# IMU.net
KiCad netlist of a schematic drawn in Altium Designer
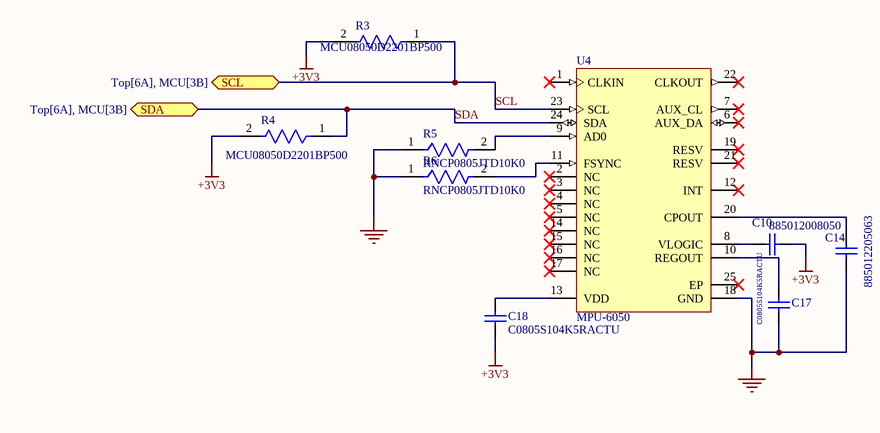
[diagram p0: IMU.SchDoc]

(export (version "E")
  (design (tool "Eeschema 10.0.6"))
  (components
    (comp (ref "C10")
      (value "885012008050")
      (footprint "WCAP-CSGP_1206_L3.2W1.6H0.8")
      (description "WCAP-CSGP 1206 (3216Metric) Ceramic Capacitor 0.126Lx0.063W 3.20mmx1.60mm C0G NP0 ±5% 1500pF")
      (fields (field (name "TOLERANCE") "5%"))
      (libsource (lib "Altium Content Vault") (part "Capacitor_Non-Polarized"))
    )
    (comp (ref "C14")
      (value "885012205063")
      (footprint "WCAP-CSGP_0402_L1W0.5H0.5")
      (description "Cap Ceramic 0.0022uF 50V X7R 10% Pad SMD 0402 125C T/R")
      (fields (field (name "TOLERANCE") "10%"))
      (libsource (lib "Altium Content Vault") (part "Capacitor_Non-Polarized"))
    )
    (comp (ref "C17")
      (value "C0805S104K5RACTU")
      (footprint "CAPC2013X145X50NL20T25")
      (fields (field (name "MANUFACTURER") "Kemet"))
      (libsource (lib "Altium Content Vault") (part "CAP"))
    )
    (comp (ref "C18")
      (value "C0805S104K5RACTU")
      (footprint "CAPC2013X145X50NL20T25")
      (fields (field (name "MANUFACTURER") "Kemet"))
      (libsource (lib "Altium Content Vault") (part "CAP"))
    )
    (comp (ref "R3")
      (value "MCU08050D2201BP500")
      (footprint "FP-MCU0805-MFG")
      (description "RES 1.05K OHM 0.5% 1/5W 0805")
      (fields (field (name "TOLERANCE") "0.1%"))
      (libsource (lib "Altium Content Vault") (part "1029c3af85768c4190bb7ad29bc67b5"))
    )
    (comp (ref "R4")
      (value "MCU08050D2201BP500")
      (footprint "FP-MCU0805-MFG")
      (description "RES 1.05K OHM 0.5% 1/5W 0805")
      (fields (field (name "TOLERANCE") "0.1%"))
      (libsource (lib "Altium Content Vault") (part "1029c3af85768c4190bb7ad29bc67b5"))
    )
    (comp (ref "R5")
      (value "RNCP0805JTD10K0")
      (footprint "FP-RNCP0805-IPC_B")
      (description "10kΩ ±5% 0.25W 0805 High Power Anti-Sulfur Thin Film Chip Resistor")
      (fields (field (name "TOLERANCE") "5%"))
      (libsource (lib "Altium Content Vault") (part "1029c3af85768c4190bb7ad29bc67b5"))
    )
    (comp (ref "R6")
      (value "RNCP0805JTD10K0")
      (footprint "FP-RNCP0805-IPC_B")
      (description "10kΩ ±5% 0.25W 0805 High Power Anti-Sulfur Thin Film Chip Resistor")
      (fields (field (name "TOLERANCE") "5%"))
      (libsource (lib "Altium Content Vault") (part "1029c3af85768c4190bb7ad29bc67b5"))
    )
    (comp (ref "U4")
      (value "MPU-6050")
      (footprint "IS-QFN-24_V")
      (fields (field (name "MANUFACTURER") "InvenSense"))
      (libsource (lib "Altium Content Vault") (part "IS-MPU-6050-QFN-24"))
    )
  )
  (nets
    (net (code "1") (name "+3V3") (class "Default")
      (node (ref "C10") (pin "2") (pinfunction "2_2") (pintype "passive"))
      (node (ref "C18") (pin "1") (pinfunction "1_1") (pintype "passive"))
      (node (ref "R3") (pin "2") (pinfunction "2_2") (pintype "passive"))
      (node (ref "R4") (pin "2") (pinfunction "2_2") (pintype "passive"))
    )
    (net (code "2") (name "/SCL") (class "Default")
      (node (ref "R3") (pin "1") (pinfunction "1_1") (pintype "passive"))
      (node (ref "U4") (pin "23") (pinfunction "SCL_23") (pintype "input"))
    )
    (net (code "3") (name "/SDA") (class "Default")
      (node (ref "R4") (pin "1") (pinfunction "1_1") (pintype "passive"))
      (node (ref "U4") (pin "24") (pinfunction "SDA_24") (pintype "bidirectional"))
    )
    (net (code "4") (name "<NO NET>") (class "Default")
      (node (ref "C14") (pin "1") (pinfunction "1_1") (pintype "passive"))
      (node (ref "C17") (pin "1") (pinfunction "1_1") (pintype "passive"))
      (node (ref "R5") (pin "1") (pinfunction "1_1") (pintype "passive"))
      (node (ref "R6") (pin "1") (pinfunction "1_1") (pintype "passive"))
      (node (ref "U4") (pin "18") (pinfunction "GND_18") (pintype "power_in"))
    )
    (net (code "5") (name "Net-(U4-AD0)") (class "Default")
      (node (ref "R5") (pin "2") (pinfunction "2_2") (pintype "passive"))
      (node (ref "U4") (pin "9") (pinfunction "AD0_9") (pintype "input"))
    )
    (net (code "6") (name "Net-(U4-CPOUT)") (class "Default")
      (node (ref "C14") (pin "2") (pinfunction "2_2") (pintype "passive"))
      (node (ref "U4") (pin "20") (pinfunction "CPOUT_20") (pintype "passive"))
    )
    (net (code "7") (name "Net-(U4-FSYNC)") (class "Default")
      (node (ref "R6") (pin "2") (pinfunction "2_2") (pintype "passive"))
      (node (ref "U4") (pin "11") (pinfunction "FSYNC_11") (pintype "input"))
    )
    (net (code "8") (name "Net-(U4-REGOUT)") (class "Default")
      (node (ref "C17") (pin "2") (pinfunction "2_2") (pintype "passive"))
      (node (ref "U4") (pin "10") (pinfunction "REGOUT_10") (pintype "passive"))
    )
    (net (code "9") (name "Net-(U4-VDD)") (class "Default")
      (node (ref "C18") (pin "2") (pinfunction "2_2") (pintype "passive"))
      (node (ref "U4") (pin "13") (pinfunction "VDD_13") (pintype "power_in"))
    )
    (net (code "10") (name "Net-(U4-VLOGIC)") (class "Default")
      (node (ref "C10") (pin "1") (pinfunction "1_1") (pintype "passive"))
      (node (ref "U4") (pin "8") (pinfunction "VLOGIC_8") (pintype "power_in"))
    )
    (net (code "11") (name "unconnected-(U4-AUX_CL-Pad7)") (class "Default")
      (node (ref "U4") (pin "7") (pinfunction "AUX_CL_7") (pintype "output+no_connect"))
    )
    (net (code "12") (name "unconnected-(U4-AUX_DA-Pad6)") (class "Default")
      (node (ref "U4") (pin "6") (pinfunction "AUX_DA_6") (pintype "bidirectional+no_connect"))
    )
    (net (code "13") (name "unconnected-(U4-CLKIN-Pad1)") (class "Default")
      (node (ref "U4") (pin "1") (pinfunction "CLKIN_1") (pintype "input+no_connect"))
    )
    (net (code "14") (name "unconnected-(U4-CLKOUT-Pad22)") (class "Default")
      (node (ref "U4") (pin "22") (pinfunction "CLKOUT_22") (pintype "output+no_connect"))
    )
    (net (code "15") (name "unconnected-(U4-EP-Pad25)") (class "Default")
      (node (ref "U4") (pin "25") (pinfunction "EP_25") (pintype "power_in+no_connect"))
    )
    (net (code "16") (name "unconnected-(U4-INT-Pad12)") (class "Default")
      (node (ref "U4") (pin "12") (pinfunction "INT_12") (pintype "open_collector+no_connect"))
    )
    (net (code "17") (name "unconnected-(U4-NC-Pad2)") (class "Default")
      (node (ref "U4") (pin "2") (pinfunction "NC_2") (pintype "passive+no_connect"))
    )
    (net (code "18") (name "unconnected-(U4-NC-Pad3)") (class "Default")
      (node (ref "U4") (pin "3") (pinfunction "NC_3") (pintype "passive+no_connect"))
    )
    (net (code "19") (name "unconnected-(U4-NC-Pad4)") (class "Default")
      (node (ref "U4") (pin "4") (pinfunction "NC_4") (pintype "passive+no_connect"))
    )
    (net (code "20") (name "unconnected-(U4-NC-Pad5)") (class "Default")
      (node (ref "U4") (pin "5") (pinfunction "NC_5") (pintype "passive+no_connect"))
    )
    (net (code "21") (name "unconnected-(U4-NC-Pad14)") (class "Default")
      (node (ref "U4") (pin "14") (pinfunction "NC_14") (pintype "passive+no_connect"))
    )
    (net (code "22") (name "unconnected-(U4-NC-Pad15)") (class "Default")
      (node (ref "U4") (pin "15") (pinfunction "NC_15") (pintype "passive+no_connect"))
    )
    (net (code "23") (name "unconnected-(U4-NC-Pad16)") (class "Default")
      (node (ref "U4") (pin "16") (pinfunction "NC_16") (pintype "passive+no_connect"))
    )
    (net (code "24") (name "unconnected-(U4-NC-Pad17)") (class "Default")
      (node (ref "U4") (pin "17") (pinfunction "NC_17") (pintype "passive+no_connect"))
    )
    (net (code "25") (name "unconnected-(U4-RESV-Pad19)") (class "Default")
      (node (ref "U4") (pin "19") (pinfunction "RESV_19") (pintype "passive+no_connect"))
    )
    (net (code "26") (name "unconnected-(U4-RESV-Pad21)") (class "Default")
      (node (ref "U4") (pin "21") (pinfunction "RESV_21") (pintype "passive+no_connect"))
    )
  )
)
